# Sheet1.net
KiCad netlist of a schematic drawn in Altium Designer
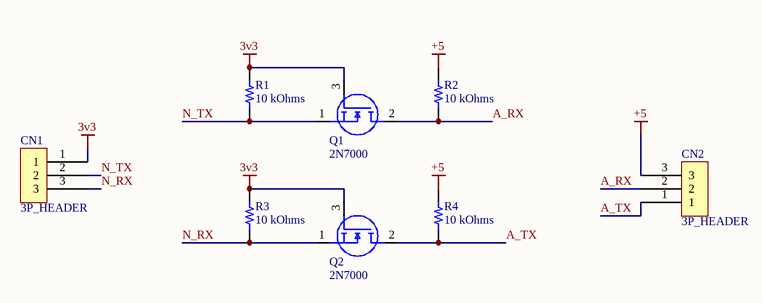
[diagram p0: Sheet1.SchDoc]

(export (version "E")
  (design (tool "Eeschema 10.0.6"))
  (components
    (comp (ref "CN1")
      (value "3P_HEADER")
      (footprint "3P_HEADER")
      (libsource (lib "Schlib1") (part "3P_HEADER"))
    )
    (comp (ref "CN2") (value "3P_HEADER") (footprint "3P_HEADER") (libsource (lib "") (part "3P_HEADER_1")))
    (comp (ref "Q1") (value "2N7000") (footprint "2N7000") (libsource (lib "Schlib1") (part "2N7000")))
    (comp (ref "Q2") (value "2N7000") (footprint "2N7000") (libsource (lib "Schlib1") (part "2N7000")))
    (comp (ref "R1")
      (value "10 kOhms")
      (footprint "RES 0805_2012")
      (description "RES 10K OHM 0.1% 1/10W 0805")
      (fields
        (field (name "PART NUMBER") "RNCS0805BKE10K0")
        (field (name "MANUFACTURER") "Stackpole Electronics Inc")
      )
      (libsource (lib "Celestial Altium Library - altium_library") (part "Resistor"))
    )
    (comp (ref "R2")
      (value "10 kOhms")
      (footprint "RES 0805_2012")
      (description "RES 10K OHM 0.1% 1/10W 0805")
      (fields
        (field (name "PART NUMBER") "RNCS0805BKE10K0")
        (field (name "MANUFACTURER") "Stackpole Electronics Inc")
      )
      (libsource (lib "Celestial Altium Library - altium_library") (part "Resistor"))
    )
    (comp (ref "R3")
      (value "10 kOhms")
      (footprint "RES 0805_2012")
      (description "RES 10K OHM 0.1% 1/10W 0805")
      (fields
        (field (name "PART NUMBER") "RNCS0805BKE10K0")
        (field (name "MANUFACTURER") "Stackpole Electronics Inc")
      )
      (libsource (lib "Celestial Altium Library - altium_library") (part "Resistor"))
    )
    (comp (ref "R4")
      (value "10 kOhms")
      (footprint "RES 0805_2012")
      (description "RES 10K OHM 0.1% 1/10W 0805")
      (fields
        (field (name "PART NUMBER") "RNCS0805BKE10K0")
        (field (name "MANUFACTURER") "Stackpole Electronics Inc")
      )
      (libsource (lib "Celestial Altium Library - altium_library") (part "Resistor"))
    )
  )
  (nets
    (net (code "1") (name "+5") (class "Default")
      (node (ref "CN2") (pin "3") (pinfunction "3_3") (pintype "passive"))
      (node (ref "R2") (pin "2") (pinfunction "2_2") (pintype "passive"))
      (node (ref "R4") (pin "2") (pinfunction "2_2") (pintype "passive"))
    )
    (net (code "2") (name "/A_RX") (class "Default")
      (node (ref "CN2") (pin "2") (pinfunction "2_2") (pintype "passive"))
      (node (ref "Q1") (pin "2") (pinfunction "D_2") (pintype "passive"))
      (node (ref "R2") (pin "1") (pinfunction "1_1") (pintype "passive"))
    )
    (net (code "3") (name "/A_TX") (class "Default")
      (node (ref "CN2") (pin "1") (pinfunction "1_1") (pintype "passive"))
      (node (ref "Q2") (pin "2") (pinfunction "D_2") (pintype "passive"))
      (node (ref "R4") (pin "1") (pinfunction "1_1") (pintype "passive"))
    )
    (net (code "4") (name "/N_RX") (class "Default")
      (node (ref "CN1") (pin "3") (pinfunction "3_3") (pintype "passive"))
      (node (ref "Q2") (pin "1") (pinfunction "S_1") (pintype "passive"))
      (node (ref "R3") (pin "1") (pinfunction "1_1") (pintype "passive"))
    )
    (net (code "5") (name "/N_TX") (class "Default")
      (node (ref "CN1") (pin "2") (pinfunction "2_2") (pintype "passive"))
      (node (ref "Q1") (pin "1") (pinfunction "S_1") (pintype "passive"))
      (node (ref "R1") (pin "1") (pinfunction "1_1") (pintype "passive"))
    )
    (net (code "6") (name "3v3") (class "Default")
      (node (ref "CN1") (pin "1") (pinfunction "1_1") (pintype "passive"))
      (node (ref "Q1") (pin "3") (pinfunction "G_3") (pintype "passive"))
      (node (ref "Q2") (pin "3") (pinfunction "G_3") (pintype "passive"))
      (node (ref "R1") (pin "2") (pinfunction "2_2") (pintype "passive"))
      (node (ref "R3") (pin "2") (pinfunction "2_2") (pintype "passive"))
    )
  )
)
